# master_brandon.net
KiCad netlist of a schematic drawn in EAGLE
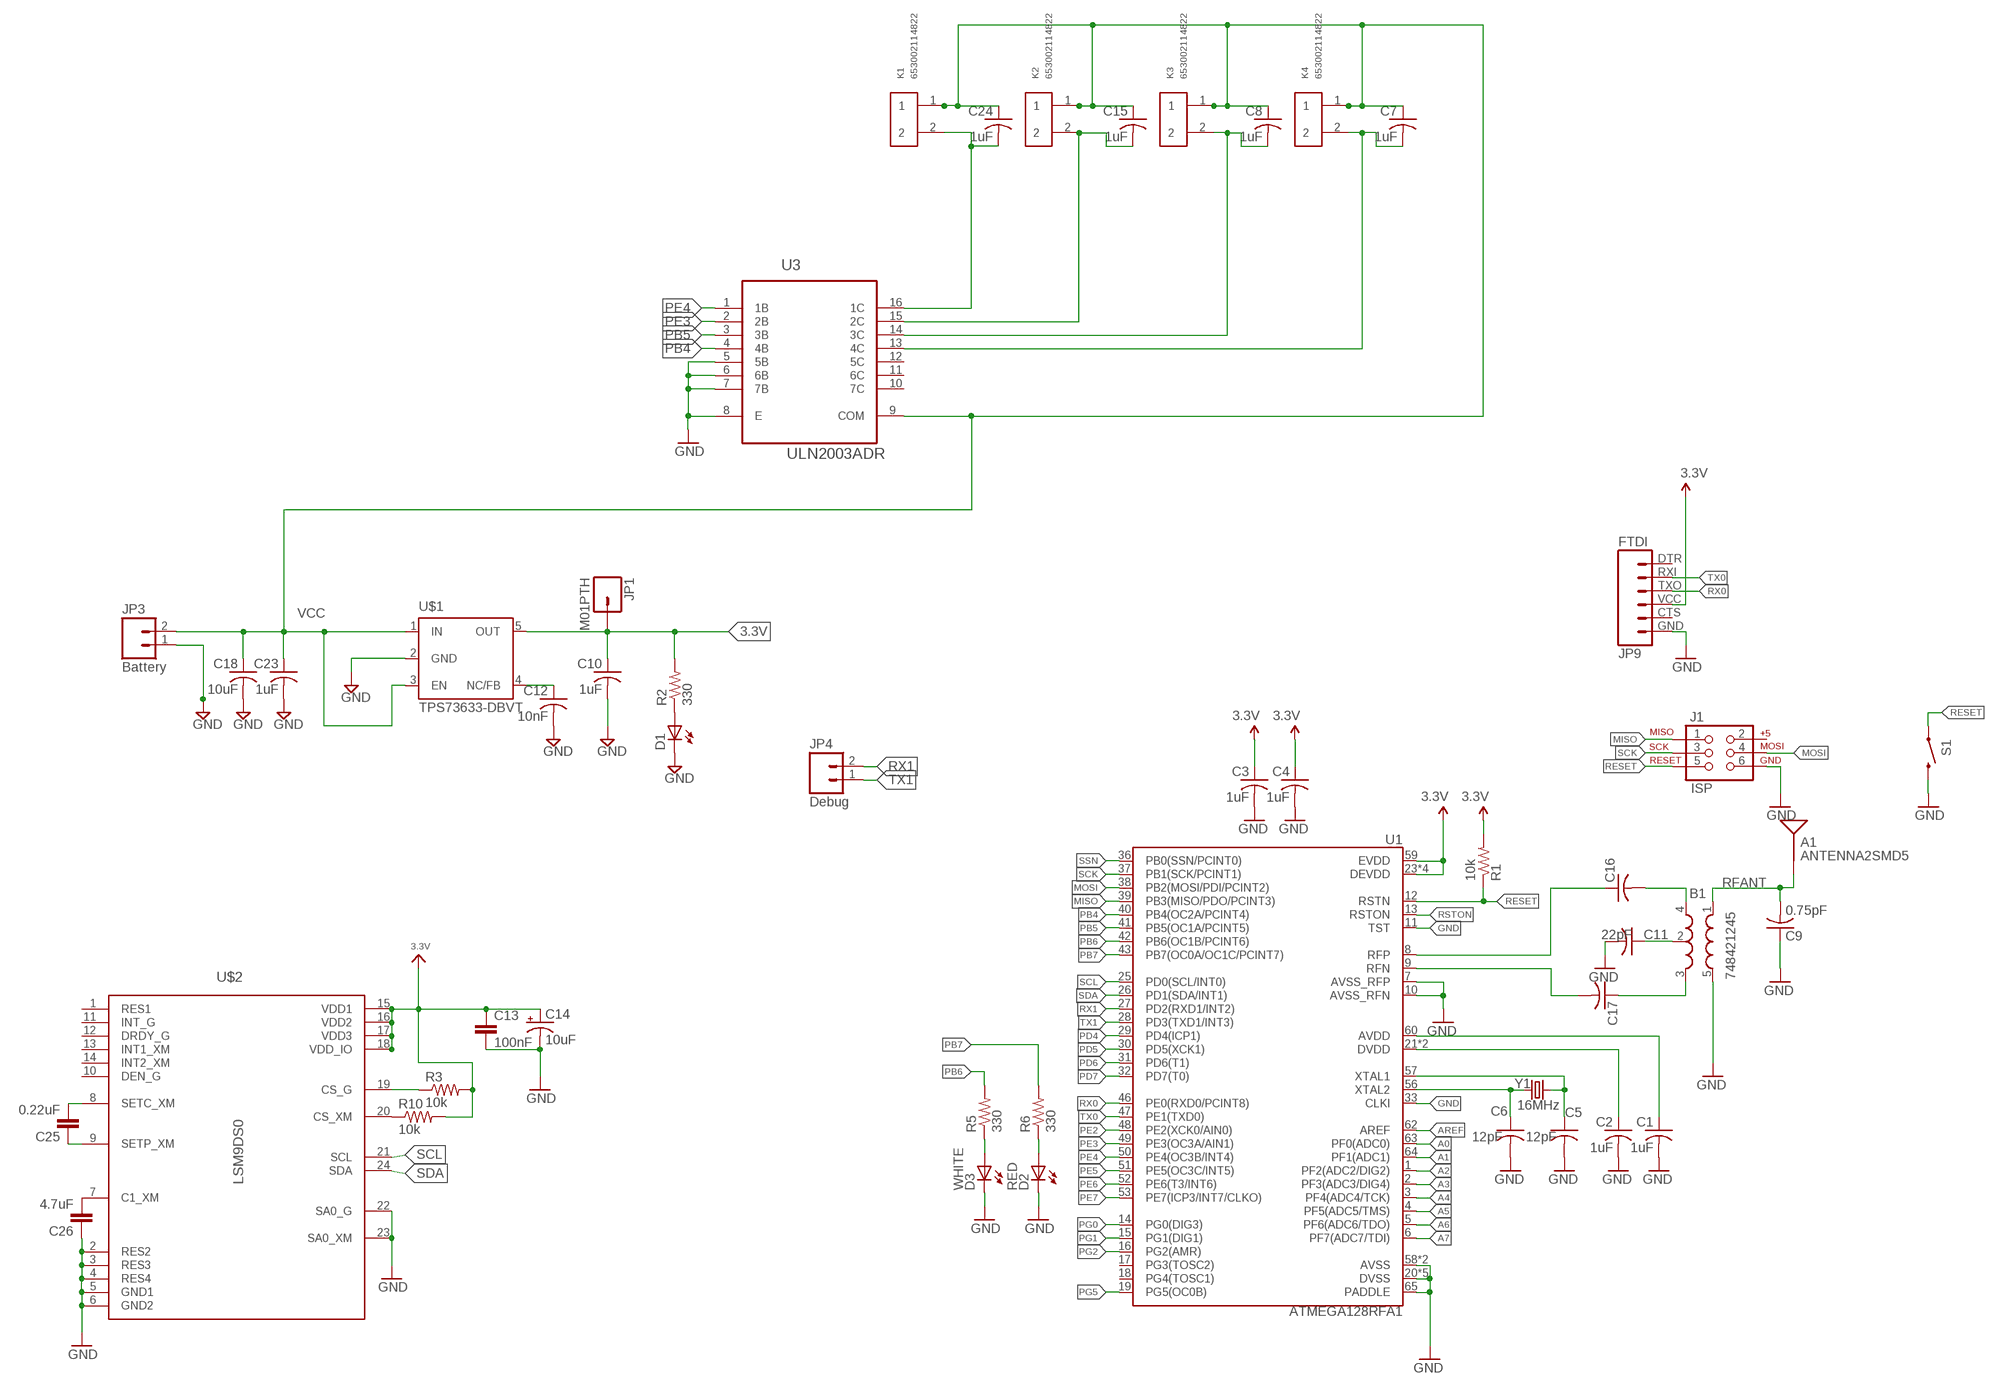
[diagram p0: schematic, sheet 1]

(export (version "E")
  (design (tool "Eeschema 10.0.6"))
  (components
    (comp (ref "A1")
      (value "ANTENNA2SMD5")
      (footprint "eagle-import:ANTENNA-CHIP5")
      (libsource (lib "eagle-import") (part "ANTENNA2SMD5"))
    )
    (comp (ref "B1")
      (value "748421245")
      (footprint "eagle-import:BALUN")
      (libsource (lib "eagle-import") (part "BALUN0805"))
    )
    (comp (ref "C1")
      (value "1uF")
      (footprint "eagle-import:C0805")
      (libsource (lib "eagle-import") (part "C-USC0805"))
    )
    (comp (ref "C2")
      (value "1uF")
      (footprint "eagle-import:C0805")
      (libsource (lib "eagle-import") (part "C-USC0805"))
    )
    (comp (ref "C3")
      (value "1uF")
      (footprint "eagle-import:C0805")
      (libsource (lib "eagle-import") (part "C-USC0805"))
    )
    (comp (ref "C4")
      (value "1uF")
      (footprint "eagle-import:C0805")
      (libsource (lib "eagle-import") (part "C-USC0805"))
    )
    (comp (ref "C5")
      (value "12pF")
      (footprint "eagle-import:C0805")
      (libsource (lib "eagle-import") (part "C-USC0805"))
    )
    (comp (ref "C6")
      (value "12pF")
      (footprint "eagle-import:C0805")
      (libsource (lib "eagle-import") (part "C-USC0805"))
    )
    (comp (ref "C7")
      (value "1uF")
      (footprint "eagle-import:C0805")
      (libsource (lib "eagle-import") (part "C-USC0805"))
    )
    (comp (ref "C8")
      (value "1uF")
      (footprint "eagle-import:C0805")
      (libsource (lib "eagle-import") (part "C-USC0805"))
    )
    (comp (ref "C9")
      (value "0.75pF")
      (footprint "eagle-import:C0805")
      (libsource (lib "eagle-import") (part "C-USC0805"))
    )
    (comp (ref "C10")
      (value "1uF")
      (footprint "eagle-import:C0805")
      (libsource (lib "eagle-import") (part "C-USC0805"))
    )
    (comp (ref "C11")
      (value "22pF")
      (footprint "eagle-import:C0805")
      (libsource (lib "eagle-import") (part "C-USC0805"))
    )
    (comp (ref "C12")
      (value "10nF")
      (footprint "eagle-import:C0805")
      (libsource (lib "eagle-import") (part "C-USC0805"))
    )
    (comp (ref "C13")
      (value "100nF")
      (footprint "eagle-import:0603-CAP")
      (libsource (lib "eagle-import") (part "CAP0603-CAP"))
    )
    (comp (ref "C14")
      (value "10uF")
      (footprint "eagle-import:EIA3528")
      (libsource (lib "eagle-import") (part "10UF-20V-10%(TANT)"))
    )
    (comp (ref "C15")
      (value "1uF")
      (footprint "eagle-import:C0805")
      (libsource (lib "eagle-import") (part "C-USC0805"))
    )
    (comp (ref "C16")
      (value "C-USC0805")
      (footprint "eagle-import:C0805")
      (libsource (lib "eagle-import") (part "C-USC0805"))
    )
    (comp (ref "C17")
      (value "C-USC0805")
      (footprint "eagle-import:C0805")
      (libsource (lib "eagle-import") (part "C-USC0805"))
    )
    (comp (ref "C18")
      (value "10uF")
      (footprint "eagle-import:C0805")
      (libsource (lib "eagle-import") (part "C-USC0805"))
    )
    (comp (ref "C23")
      (value "1uF")
      (footprint "eagle-import:C0805")
      (libsource (lib "eagle-import") (part "C-USC0805"))
    )
    (comp (ref "C24")
      (value "1uF")
      (footprint "eagle-import:C0805")
      (libsource (lib "eagle-import") (part "C-USC0805"))
    )
    (comp (ref "C25")
      (value "0.22uF")
      (footprint "eagle-import:0603-CAP")
      (libsource (lib "eagle-import") (part "CAP0603-CAP"))
    )
    (comp (ref "C26")
      (value "4.7uF")
      (footprint "eagle-import:0603-CAP")
      (libsource (lib "eagle-import") (part "CAP0603-CAP"))
    )
    (comp (ref "D1")
      (value "LEDSML0603")
      (footprint "eagle-import:SML0603")
      (libsource (lib "eagle-import") (part "master_devon_LEDSML0603"))
    )
    (comp (ref "D2")
      (value "RED")
      (footprint "eagle-import:CHIPLED_0603")
      (libsource (lib "eagle-import") (part "LEDCHIPLED_0603"))
    )
    (comp (ref "D3")
      (value "WHITE")
      (footprint "eagle-import:CHIPLED_0603")
      (libsource (lib "eagle-import") (part "LEDCHIPLED_0603"))
    )
    (comp (ref "J1")
      (value "ISP")
      (footprint "eagle-import:2X3-NS")
      (libsource (lib "eagle-import") (part "AVR_SPI_PRG_6NS"))
    )
    (comp (ref "JP1")
      (value "M01PTH")
      (footprint "eagle-import:1X01")
      (libsource (lib "eagle-import") (part "M01PTH"))
    )
    (comp (ref "JP3")
      (value "Battery")
      (footprint "eagle-import:1X02")
      (libsource (lib "eagle-import") (part "M02PTH"))
    )
    (comp (ref "JP4")
      (value "Debug")
      (footprint "eagle-import:1X02")
      (libsource (lib "eagle-import") (part "M02PTH"))
    )
    (comp (ref "JP9")
      (value "FTDI")
      (footprint "eagle-import:FTDI_BASIC")
      (libsource (lib "eagle-import") (part "FTDI_BASICPTH"))
    )
    (comp (ref "K1")
      (value "653002114822")
      (footprint "eagle-import:653002114822")
      (libsource (lib "eagle-import") (part "653002114822"))
    )
    (comp (ref "K2")
      (value "653002114822")
      (footprint "eagle-import:653002114822")
      (libsource (lib "eagle-import") (part "653002114822"))
    )
    (comp (ref "K3")
      (value "653002114822")
      (footprint "eagle-import:653002114822")
      (libsource (lib "eagle-import") (part "653002114822"))
    )
    (comp (ref "K4")
      (value "653002114822")
      (footprint "eagle-import:653002114822")
      (libsource (lib "eagle-import") (part "653002114822"))
    )
    (comp (ref "R1")
      (value "10k")
      (footprint "eagle-import:R0805")
      (libsource (lib "eagle-import") (part "R-US_R0805"))
    )
    (comp (ref "R2")
      (value "330")
      (footprint "eagle-import:R0805")
      (libsource (lib "eagle-import") (part "R-US_R0805"))
    )
    (comp (ref "R3")
      (value "10k")
      (footprint "eagle-import:0805")
      (libsource (lib "eagle-import") (part "RESISTOR0805-RES"))
    )
    (comp (ref "R5")
      (value "330")
      (footprint "eagle-import:0603-RES")
      (libsource (lib "eagle-import") (part "SparkFun-Resistors_RESISTOR0603-RES"))
    )
    (comp (ref "R6")
      (value "330")
      (footprint "eagle-import:0603-RES")
      (libsource (lib "eagle-import") (part "SparkFun-Resistors_RESISTOR0603-RES"))
    )
    (comp (ref "R10")
      (value "10k")
      (footprint "eagle-import:0805")
      (libsource (lib "eagle-import") (part "RESISTOR0805-RES"))
    )
    (comp (ref "S1")
      (value "SWITCH-MOMENTARY-2SMD")
      (footprint "eagle-import:TACTILE_SWITCH_SMD")
      (libsource (lib "eagle-import") (part "SWITCH-MOMENTARY-2SMD"))
    )
    (comp (ref "U$1")
      (value "TPS73633-DBVT")
      (footprint "eagle-import:SOT23-DBV")
      (libsource (lib "eagle-import") (part "TPS73633-DBVT"))
    )
    (comp (ref "U$2")
      (value "LSM9DS0")
      (footprint "eagle-import:LGA-24")
      (libsource (lib "eagle-import") (part "LSM9DS0"))
    )
    (comp (ref "U1")
      (value "ATMEGA128RFA1")
      (footprint "eagle-import:QFN-64")
      (libsource (lib "eagle-import") (part "ATMEGA128RFA1"))
    )
    (comp (ref "U3")
      (value "ULN2003ADR")
      (footprint "eagle-import:SOIC127P600X175-16N")
      (libsource (lib "eagle-import") (part "ULN2003ADR"))
    )
    (comp (ref "Y1")
      (value "16MHz")
      (footprint "eagle-import:CRYSTAL-SMD-5X3")
      (libsource (lib "eagle-import") (part "CRYSTAL5X3"))
    )
  )
  (nets
    (net (code "1") (name "/RFANT") (class "Default")
      (node (ref "A1") (pin "FEED") (pinfunction "SIGNAL_FEED") (pintype "bidirectional"))
      (node (ref "B1") (pin "1") (pinfunction "IN_1") (pintype "bidirectional"))
      (node (ref "C9") (pin "2") (pinfunction "2_2") (pintype "passive"))
    )
    (net (code "2") (name "/VCC") (class "Default")
      (node (ref "C15") (pin "1") (pinfunction "1_1") (pintype "passive"))
      (node (ref "C18") (pin "1") (pinfunction "1_1") (pintype "passive"))
      (node (ref "C23") (pin "1") (pinfunction "1_1") (pintype "passive"))
      (node (ref "C24") (pin "1") (pinfunction "1_1") (pintype "passive"))
      (node (ref "C7") (pin "1") (pinfunction "1_1") (pintype "passive"))
      (node (ref "C8") (pin "1") (pinfunction "1_1") (pintype "passive"))
      (node (ref "JP3") (pin "2") (pinfunction "2_2") (pintype "passive"))
      (node (ref "K1") (pin "1") (pinfunction "1_1") (pintype "bidirectional"))
      (node (ref "K2") (pin "1") (pinfunction "1_1") (pintype "bidirectional"))
      (node (ref "K3") (pin "1") (pinfunction "1_1") (pintype "bidirectional"))
      (node (ref "K4") (pin "1") (pinfunction "1_1") (pintype "bidirectional"))
      (node (ref "U$1") (pin "1") (pinfunction "IN_1") (pintype "input"))
      (node (ref "U$1") (pin "3") (pinfunction "EN_3") (pintype "power_in"))
      (node (ref "U3") (pin "9") (pinfunction "COM_9") (pintype "output"))
    )
    (net (code "3") (name "3.3V") (class "Default")
      (node (ref "C10") (pin "1") (pinfunction "1_1") (pintype "passive"))
      (node (ref "C13") (pin "1") (pinfunction "1_1") (pintype "passive"))
      (node (ref "C14") (pin "A") (pinfunction "+_A") (pintype "passive"))
      (node (ref "C3") (pin "1") (pinfunction "1_1") (pintype "passive"))
      (node (ref "C4") (pin "1") (pinfunction "1_1") (pintype "passive"))
      (node (ref "JP1") (pin "1") (pinfunction "1_1") (pintype "passive"))
      (node (ref "JP9") (pin "VCC") (pinfunction "4_VCC") (pintype "passive"))
      (node (ref "R1") (pin "2") (pinfunction "2_2") (pintype "passive"))
      (node (ref "R10") (pin "2") (pinfunction "2_2") (pintype "passive"))
      (node (ref "R2") (pin "2") (pinfunction "2_2") (pintype "passive"))
      (node (ref "R3") (pin "2") (pinfunction "2_2") (pintype "passive"))
      (node (ref "U$1") (pin "5") (pinfunction "OUT_5") (pintype "passive"))
      (node (ref "U$2") (pin "15") (pinfunction "VDD1_15") (pintype "bidirectional"))
      (node (ref "U$2") (pin "16") (pinfunction "VDD2_16") (pintype "bidirectional"))
      (node (ref "U$2") (pin "17") (pinfunction "VDD3_17") (pintype "bidirectional"))
      (node (ref "U$2") (pin "18") (pinfunction "VDD_IO_18") (pintype "bidirectional"))
      (node (ref "U1") (pin "23") (pinfunction "DEVDD_23") (pintype "bidirectional"))
      (node (ref "U1") (pin "34") (pinfunction "DEVDD_34") (pintype "bidirectional"))
      (node (ref "U1") (pin "44") (pinfunction "DEVDD_44") (pintype "bidirectional"))
      (node (ref "U1") (pin "54") (pinfunction "DEVDD_54") (pintype "bidirectional"))
      (node (ref "U1") (pin "59") (pinfunction "EVDD_59") (pintype "bidirectional"))
    )
    (net (code "4") (name "A0") (class "Default")
      (node (ref "U1") (pin "63") (pinfunction "PF0(ADC0)_63") (pintype "bidirectional"))
    )
    (net (code "5") (name "A1") (class "Default")
      (node (ref "U1") (pin "64") (pinfunction "PF1(ADC1)_64") (pintype "bidirectional"))
    )
    (net (code "6") (name "A2") (class "Default")
      (node (ref "U1") (pin "1") (pinfunction "PF2(ADC2/DIG2)_1") (pintype "bidirectional"))
    )
    (net (code "7") (name "A3") (class "Default")
      (node (ref "U1") (pin "2") (pinfunction "PF3(ADC3/DIG4)_2") (pintype "bidirectional"))
    )
    (net (code "8") (name "A4") (class "Default")
      (node (ref "U1") (pin "3") (pinfunction "PF4(ADC4/TCK)_3") (pintype "bidirectional"))
    )
    (net (code "9") (name "A5") (class "Default")
      (node (ref "U1") (pin "4") (pinfunction "PF5(ADC5/TMS)_4") (pintype "bidirectional"))
    )
    (net (code "10") (name "A6") (class "Default")
      (node (ref "U1") (pin "5") (pinfunction "PF6(ADC6/TDO)_5") (pintype "bidirectional"))
    )
    (net (code "11") (name "A7") (class "Default")
      (node (ref "U1") (pin "6") (pinfunction "PF7(ADC7/TDI)_6") (pintype "bidirectional"))
    )
    (net (code "12") (name "AREF") (class "Default")
      (node (ref "U1") (pin "62") (pinfunction "AREF_62") (pintype "bidirectional"))
    )
    (net (code "13") (name "GND") (class "Default")
      (node (ref "B1") (pin "5") (pinfunction "GND_5") (pintype "bidirectional"))
      (node (ref "C1") (pin "2") (pinfunction "2_2") (pintype "passive"))
      (node (ref "C10") (pin "2") (pinfunction "2_2") (pintype "passive"))
      (node (ref "C11") (pin "2") (pinfunction "2_2") (pintype "passive"))
      (node (ref "C12") (pin "2") (pinfunction "2_2") (pintype "passive"))
      (node (ref "C13") (pin "2") (pinfunction "2_2") (pintype "passive"))
      (node (ref "C14") (pin "C") (pinfunction "-_C") (pintype "passive"))
      (node (ref "C18") (pin "2") (pinfunction "2_2") (pintype "passive"))
      (node (ref "C2") (pin "2") (pinfunction "2_2") (pintype "passive"))
      (node (ref "C23") (pin "2") (pinfunction "2_2") (pintype "passive"))
      (node (ref "C26") (pin "1") (pinfunction "1_1") (pintype "passive"))
      (node (ref "C3") (pin "2") (pinfunction "2_2") (pintype "passive"))
      (node (ref "C4") (pin "2") (pinfunction "2_2") (pintype "passive"))
      (node (ref "C5") (pin "2") (pinfunction "2_2") (pintype "passive"))
      (node (ref "C6") (pin "2") (pinfunction "2_2") (pintype "passive"))
      (node (ref "C9") (pin "1") (pinfunction "1_1") (pintype "passive"))
      (node (ref "D1") (pin "C") (pinfunction "C_C") (pintype "passive"))
      (node (ref "D2") (pin "C") (pinfunction "C_C") (pintype "passive"))
      (node (ref "D3") (pin "C") (pinfunction "C_C") (pintype "passive"))
      (node (ref "J1") (pin "6") (pinfunction "6_6") (pintype "passive"))
      (node (ref "JP3") (pin "1") (pinfunction "1_1") (pintype "passive"))
      (node (ref "JP9") (pin "GND") (pinfunction "6_GND") (pintype "passive"))
      (node (ref "S1") (pin "3") (pinfunction "2_3") (pintype "passive"))
      (node (ref "U$1") (pin "2") (pinfunction "GND_2") (pintype "input"))
      (node (ref "U$2") (pin "2") (pinfunction "RES2_2") (pintype "bidirectional"))
      (node (ref "U$2") (pin "22") (pinfunction "SA0_G_22") (pintype "bidirectional"))
      (node (ref "U$2") (pin "23") (pinfunction "SA0_XM_23") (pintype "bidirectional"))
      (node (ref "U$2") (pin "3") (pinfunction "RES3_3") (pintype "bidirectional"))
      (node (ref "U$2") (pin "4") (pinfunction "RES4_4") (pintype "bidirectional"))
      (node (ref "U$2") (pin "5") (pinfunction "GND1_5") (pintype "bidirectional"))
      (node (ref "U$2") (pin "6") (pinfunction "GND2_6") (pintype "bidirectional"))
      (node (ref "U1") (pin "10") (pinfunction "AVSS_RFN_10") (pintype "bidirectional"))
      (node (ref "U1") (pin "11") (pinfunction "TST_11") (pintype "bidirectional"))
      (node (ref "U1") (pin "20") (pinfunction "DVSS_20") (pintype "bidirectional"))
      (node (ref "U1") (pin "24") (pinfunction "DVSS_24") (pintype "bidirectional"))
      (node (ref "U1") (pin "33") (pinfunction "CLKI_33") (pintype "bidirectional"))
      (node (ref "U1") (pin "35") (pinfunction "DVSS_35") (pintype "bidirectional"))
      (node (ref "U1") (pin "45") (pinfunction "DVSS_45") (pintype "bidirectional"))
      (node (ref "U1") (pin "55") (pinfunction "DVSS_55") (pintype "bidirectional"))
      (node (ref "U1") (pin "58") (pinfunction "AVSS_58") (pintype "bidirectional"))
      (node (ref "U1") (pin "61") (pinfunction "AVSS_61") (pintype "bidirectional"))
      (node (ref "U1") (pin "65") (pinfunction "PADDLE_65") (pintype "bidirectional"))
      (node (ref "U1") (pin "7") (pinfunction "AVSS_RFP_7") (pintype "bidirectional"))
      (node (ref "U3") (pin "5") (pinfunction "5B_5") (pintype "input"))
      (node (ref "U3") (pin "6") (pinfunction "6B_6") (pintype "input"))
      (node (ref "U3") (pin "7") (pinfunction "7B_7") (pintype "input"))
      (node (ref "U3") (pin "8") (pinfunction "E_8") (pintype "input"))
    )
    (net (code "14") (name "MISO") (class "Default")
      (node (ref "J1") (pin "1") (pinfunction "1_1") (pintype "passive"))
      (node (ref "U1") (pin "39") (pinfunction "PB3(MISO/PDO/PCINT3)_39") (pintype "bidirectional"))
    )
    (net (code "15") (name "MOSI") (class "Default")
      (node (ref "J1") (pin "4") (pinfunction "4_4") (pintype "passive"))
      (node (ref "U1") (pin "38") (pinfunction "PB2(MOSI/PDI/PCINT2)_38") (pintype "bidirectional"))
    )
    (net (code "16") (name "Net-(B1-GND-Pad2)") (class "Default")
      (node (ref "B1") (pin "2") (pinfunction "GND_2") (pintype "bidirectional"))
      (node (ref "C11") (pin "1") (pinfunction "1_1") (pintype "passive"))
    )
    (net (code "17") (name "Net-(B1-OUT1)") (class "Default")
      (node (ref "B1") (pin "4") (pinfunction "OUT1_4") (pintype "bidirectional"))
      (node (ref "C16") (pin "2") (pinfunction "2_2") (pintype "passive"))
    )
    (net (code "18") (name "Net-(B1-OUT2)") (class "Default")
      (node (ref "B1") (pin "3") (pinfunction "OUT2_3") (pintype "bidirectional"))
      (node (ref "C17") (pin "1") (pinfunction "1_1") (pintype "passive"))
    )
    (net (code "19") (name "Net-(C2-Pad1)") (class "Default")
      (node (ref "C2") (pin "1") (pinfunction "1_1") (pintype "passive"))
      (node (ref "U1") (pin "21") (pinfunction "DVDD_21") (pintype "bidirectional"))
      (node (ref "U1") (pin "22") (pinfunction "DVDD_22") (pintype "bidirectional"))
    )
    (net (code "20") (name "Net-(D1-PadA)") (class "Default")
      (node (ref "D1") (pin "A") (pinfunction "A_A") (pintype "passive"))
      (node (ref "R2") (pin "1") (pinfunction "1_1") (pintype "passive"))
    )
    (net (code "21") (name "Net-(D2-PadA)") (class "Default")
      (node (ref "D2") (pin "A") (pinfunction "A_A") (pintype "passive"))
      (node (ref "R6") (pin "1") (pinfunction "1_1") (pintype "passive"))
    )
    (net (code "22") (name "Net-(D3-PadA)") (class "Default")
      (node (ref "D3") (pin "A") (pinfunction "A_A") (pintype "passive"))
      (node (ref "R5") (pin "1") (pinfunction "1_1") (pintype "passive"))
    )
    (net (code "23") (name "Net-(U$1-NC{slash}FB)") (class "Default")
      (node (ref "C12") (pin "1") (pinfunction "1_1") (pintype "passive"))
      (node (ref "U$1") (pin "4") (pinfunction "NC/FB_4") (pintype "passive"))
    )
    (net (code "24") (name "Net-(U$2-C1_XM)") (class "Default")
      (node (ref "C26") (pin "2") (pinfunction "2_2") (pintype "passive"))
      (node (ref "U$2") (pin "7") (pinfunction "C1_XM_7") (pintype "bidirectional"))
    )
    (net (code "25") (name "Net-(U$2-CS_G)") (class "Default")
      (node (ref "R3") (pin "1") (pinfunction "1_1") (pintype "passive"))
      (node (ref "U$2") (pin "19") (pinfunction "CS_G_19") (pintype "bidirectional"))
    )
    (net (code "26") (name "Net-(U$2-CS_XM)") (class "Default")
      (node (ref "R10") (pin "1") (pinfunction "1_1") (pintype "passive"))
      (node (ref "U$2") (pin "20") (pinfunction "CS_XM_20") (pintype "bidirectional"))
    )
    (net (code "27") (name "Net-(U$2-SETC_XM)") (class "Default")
      (node (ref "C25") (pin "2") (pinfunction "2_2") (pintype "passive"))
      (node (ref "U$2") (pin "8") (pinfunction "SETC_XM_8") (pintype "bidirectional"))
    )
    (net (code "28") (name "Net-(U$2-SETP_XM)") (class "Default")
      (node (ref "C25") (pin "1") (pinfunction "1_1") (pintype "passive"))
      (node (ref "U$2") (pin "9") (pinfunction "SETP_XM_9") (pintype "bidirectional"))
    )
    (net (code "29") (name "Net-(U1-AVDD)") (class "Default")
      (node (ref "C1") (pin "1") (pinfunction "1_1") (pintype "passive"))
      (node (ref "U1") (pin "60") (pinfunction "AVDD_60") (pintype "bidirectional"))
    )
    (net (code "30") (name "Net-(U1-RFN)") (class "Default")
      (node (ref "C17") (pin "2") (pinfunction "2_2") (pintype "passive"))
      (node (ref "U1") (pin "9") (pinfunction "RFN_9") (pintype "bidirectional"))
    )
    (net (code "31") (name "Net-(U1-RFP)") (class "Default")
      (node (ref "C16") (pin "1") (pinfunction "1_1") (pintype "passive"))
      (node (ref "U1") (pin "8") (pinfunction "RFP_8") (pintype "bidirectional"))
    )
    (net (code "32") (name "Net-(U1-XTAL1)") (class "Default")
      (node (ref "C5") (pin "1") (pinfunction "1_1") (pintype "passive"))
      (node (ref "U1") (pin "57") (pinfunction "XTAL1_57") (pintype "bidirectional"))
      (node (ref "Y1") (pin "3") (pinfunction "2_3") (pintype "passive"))
    )
    (net (code "33") (name "Net-(U1-XTAL2)") (class "Default")
      (node (ref "C6") (pin "1") (pinfunction "1_1") (pintype "passive"))
      (node (ref "U1") (pin "56") (pinfunction "XTAL2_56") (pintype "bidirectional"))
      (node (ref "Y1") (pin "1") (pinfunction "1_1") (pintype "passive"))
    )
    (net (code "34") (name "Net-(U3-1C)") (class "Default")
      (node (ref "C24") (pin "2") (pinfunction "2_2") (pintype "passive"))
      (node (ref "K1") (pin "2") (pinfunction "2_2") (pintype "bidirectional"))
      (node (ref "U3") (pin "16") (pinfunction "1C_16") (pintype "output"))
    )
    (net (code "35") (name "Net-(U3-2C)") (class "Default")
      (node (ref "C15") (pin "2") (pinfunction "2_2") (pintype "passive"))
      (node (ref "K2") (pin "2") (pinfunction "2_2") (pintype "bidirectional"))
      (node (ref "U3") (pin "15") (pinfunction "2C_15") (pintype "output"))
    )
    (net (code "36") (name "Net-(U3-3C)") (class "Default")
      (node (ref "C8") (pin "2") (pinfunction "2_2") (pintype "passive"))
      (node (ref "K3") (pin "2") (pinfunction "2_2") (pintype "bidirectional"))
      (node (ref "U3") (pin "14") (pinfunction "3C_14") (pintype "output"))
    )
    (net (code "37") (name "Net-(U3-4C)") (class "Default")
      (node (ref "C7") (pin "2") (pinfunction "2_2") (pintype "passive"))
      (node (ref "K4") (pin "2") (pinfunction "2_2") (pintype "bidirectional"))
      (node (ref "U3") (pin "13") (pinfunction "4C_13") (pintype "output"))
    )
    (net (code "38") (name "PB4") (class "Default")
      (node (ref "U1") (pin "40") (pinfunction "PB4(OC2A/PCINT4)_40") (pintype "bidirectional"))
      (node (ref "U3") (pin "4") (pinfunction "4B_4") (pintype "input"))
    )
    (net (code "39") (name "PB5") (class "Default")
      (node (ref "U1") (pin "41") (pinfunction "PB5(OC1A/PCINT5)_41") (pintype "bidirectional"))
      (node (ref "U3") (pin "3") (pinfunction "3B_3") (pintype "input"))
    )
    (net (code "40") (name "PB6") (class "Default")
      (node (ref "R5") (pin "2") (pinfunction "2_2") (pintype "passive"))
      (node (ref "U1") (pin "42") (pinfunction "PB6(OC1B/PCINT6)_42") (pintype "bidirectional"))
    )
    (net (code "41") (name "PB7") (class "Default")
      (node (ref "R6") (pin "2") (pinfunction "2_2") (pintype "passive"))
      (node (ref "U1") (pin "43") (pinfunction "PB7(OC0A/OC1C/PCINT7)_43") (pintype "bidirectional"))
    )
    (net (code "42") (name "PD4") (class "Default")
      (node (ref "U1") (pin "29") (pinfunction "PD4(ICP1)_29") (pintype "bidirectional"))
    )
    (net (code "43") (name "PD5") (class "Default")
      (node (ref "U1") (pin "30") (pinfunction "PD5(XCK1)_30") (pintype "bidirectional"))
    )
    (net (code "44") (name "PD6") (class "Default")
      (node (ref "U1") (pin "31") (pinfunction "PD6(T1)_31") (pintype "bidirectional"))
    )
    (net (code "45") (name "PD7") (class "Default")
      (node (ref "U1") (pin "32") (pinfunction "PD7(T0)_32") (pintype "bidirectional"))
    )
    (net (code "46") (name "PE2") (class "Default")
      (node (ref "U1") (pin "48") (pinfunction "PE2(XCK0/AIN0)_48") (pintype "bidirectional"))
    )
    (net (code "47") (name "PE3") (class "Default")
      (node (ref "U1") (pin "49") (pinfunction "PE3(OC3A/AIN1)_49") (pintype "bidirectional"))
      (node (ref "U3") (pin "2") (pinfunction "2B_2") (pintype "input"))
    )
    (net (code "48") (name "PE4") (class "Default")
      (node (ref "U1") (pin "50") (pinfunction "PE4(OC3B/INT4)_50") (pintype "bidirectional"))
      (node (ref "U3") (pin "1") (pinfunction "1B_1") (pintype "input"))
    )
    (net (code "49") (name "PE5") (class "Default")
      (node (ref "U1") (pin "51") (pinfunction "PE5(OC3C/INT5)_51") (pintype "bidirectional"))
    )
    (net (code "50") (name "PE6") (class "Default")
      (node (ref "U1") (pin "52") (pinfunction "PE6(T3/INT6)_52") (pintype "bidirectional"))
    )
    (net (code "51") (name "PE7") (class "Default")
      (node (ref "U1") (pin "53") (pinfunction "PE7(ICP3/INT7/CLKO)_53") (pintype "bidirectional"))
    )
    (net (code "52") (name "PG0") (class "Default")
      (node (ref "U1") (pin "14") (pinfunction "PG0(DIG3)_14") (pintype "bidirectional"))
    )
    (net (code "53") (name "PG1") (class "Default")
      (node (ref "U1") (pin "15") (pinfunction "PG1(DIG1)_15") (pintype "bidirectional"))
    )
    (net (code "54") (name "PG2") (class "Default")
      (node (ref "U1") (pin "16") (pinfunction "PG2(AMR)_16") (pintype "bidirectional"))
    )
    (net (code "55") (name "PG5") (class "Default")
      (node (ref "U1") (pin "19") (pinfunction "PG5(OC0B)_19") (pintype "bidirectional"))
    )
    (net (code "56") (name "RESET") (class "Default")
      (node (ref "J1") (pin "5") (pinfunction "5_5") (pintype "passive"))
      (node (ref "R1") (pin "1") (pinfunction "1_1") (pintype "passive"))
      (node (ref "S1") (pin "1") (pinfunction "1_1") (pintype "passive"))
      (node (ref "U1") (pin "12") (pinfunction "RSTN_12") (pintype "bidirectional"))
    )
    (net (code "57") (name "RSTON") (class "Default")
      (node (ref "U1") (pin "13") (pinfunction "RSTON_13") (pintype "bidirectional"))
    )
    (net (code "58") (name "RX0") (class "Default")
      (node (ref "JP9") (pin "TXO") (pinfunction "3_TXO") (pintype "passive"))
      (node (ref "U1") (pin "46") (pinfunction "PE0(RXD0/PCINT8)_46") (pintype "bidirectional"))
    )
    (net (code "59") (name "RX1") (class "Default")
      (node (ref "JP4") (pin "2") (pinfunction "2_2") (pintype "passive"))
      (node (ref "U1") (pin "27") (pinfunction "PD2(RXD1/INT2)_27") (pintype "bidirectional"))
    )
    (net (code "60") (name "SCK") (class "Default")
      (node (ref "J1") (pin "3") (pinfunction "3_3") (pintype "passive"))
      (node (ref "U1") (pin "37") (pinfunction "PB1(SCK/PCINT1)_37") (pintype "bidirectional"))
    )
    (net (code "61") (name "SCL") (class "Default")
      (node (ref "U$2") (pin "21") (pinfunction "SCL_21") (pintype "bidirectional"))
      (node (ref "U1") (pin "25") (pinfunction "PD0(SCL/INT0)_25") (pintype "bidirectional"))
    )
    (net (code "62") (name "SDA") (class "Default")
      (node (ref "U$2") (pin "24") (pinfunction "SDA_24") (pintype "bidirectional"))
      (node (ref "U1") (pin "26") (pinfunction "PD1(SDA/INT1)_26") (pintype "bidirectional"))
    )
    (net (code "63") (name "SSN") (class "Default")
      (node (ref "U1") (pin "36") (pinfunction "PB0(SSN/PCINT0)_36") (pintype "bidirectional"))
    )
    (net (code "64") (name "TX0") (class "Default")
      (node (ref "JP9") (pin "RXI") (pinfunction "2_RXI") (pintype "passive"))
      (node (ref "U1") (pin "47") (pinfunction "PE1(TXD0)_47") (pintype "bidirectional"))
    )
    (net (code "65") (name "TX1") (class "Default")
      (node (ref "JP4") (pin "1") (pinfunction "1_1") (pintype "passive"))
      (node (ref "U1") (pin "28") (pinfunction "PD3(TXD1/INT3)_28") (pintype "bidirectional"))
    )
    (net (code "66") (name "unconnected-(J1-Pad2)") (class "Default")
      (node (ref "J1") (pin "2") (pinfunction "2_2") (pintype "passive"))
    )
    (net (code "67") (name "unconnected-(JP9-1-PadDTR)") (class "Default")
      (node (ref "JP9") (pin "DTR") (pinfunction "1_DTR") (pintype "passive"))
    )
    (net (code "68") (name "unconnected-(JP9-5-PadCTS)") (class "Default")
      (node (ref "JP9") (pin "CTS") (pinfunction "5_CTS") (pintype "passive"))
    )
    (net (code "69") (name "unconnected-(U$2-DEN_G-Pad10)") (class "Default")
      (node (ref "U$2") (pin "10") (pinfunction "DEN_G_10") (pintype "bidirectional"))
    )
    (net (code "70") (name "unconnected-(U$2-DRDY_G-Pad12)") (class "Default")
      (node (ref "U$2") (pin "12") (pinfunction "DRDY_G_12") (pintype "bidirectional"))
    )
    (net (code "71") (name "unconnected-(U$2-INT1_XM-Pad13)") (class "Default")
      (node (ref "U$2") (pin "13") (pinfunction "INT1_XM_13") (pintype "bidirectional"))
    )
    (net (code "72") (name "unconnected-(U$2-INT2_XM-Pad14)") (class "Default")
      (node (ref "U$2") (pin "14") (pinfunction "INT2_XM_14") (pintype "bidirectional"))
    )
    (net (code "73") (name "unconnected-(U$2-INT_G-Pad11)") (class "Default")
      (node (ref "U$2") (pin "11") (pinfunction "INT_G_11") (pintype "bidirectional"))
    )
    (net (code "74") (name "unconnected-(U$2-RES1-Pad1)") (class "Default")
      (node (ref "U$2") (pin "1") (pinfunction "RES1_1") (pintype "bidirectional"))
    )
    (net (code "75") (name "unconnected-(U1-PG3(TOSC2)-Pad17)") (class "Default")
      (node (ref "U1") (pin "17") (pinfunction "PG3(TOSC2)_17") (pintype "bidirectional"))
    )
    (net (code "76") (name "unconnected-(U1-PG4(TOSC1)-Pad18)") (class "Default")
      (node (ref "U1") (pin "18") (pinfunction "PG4(TOSC1)_18") (pintype "bidirectional"))
    )
    (net (code "77") (name "unconnected-(U3-5C-Pad12)") (class "Default")
      (node (ref "U3") (pin "12") (pinfunction "5C_12") (pintype "output"))
    )
    (net (code "78") (name "unconnected-(U3-6C-Pad11)") (class "Default")
      (node (ref "U3") (pin "11") (pinfunction "6C_11") (pintype "output"))
    )
    (net (code "79") (name "unconnected-(U3-7C-Pad10)") (class "Default")
      (node (ref "U3") (pin "10") (pinfunction "7C_10") (pintype "output"))
    )
  )
)
